# 4_COMMUNICATION.net
KiCad netlist of a schematic drawn in Altium Designer
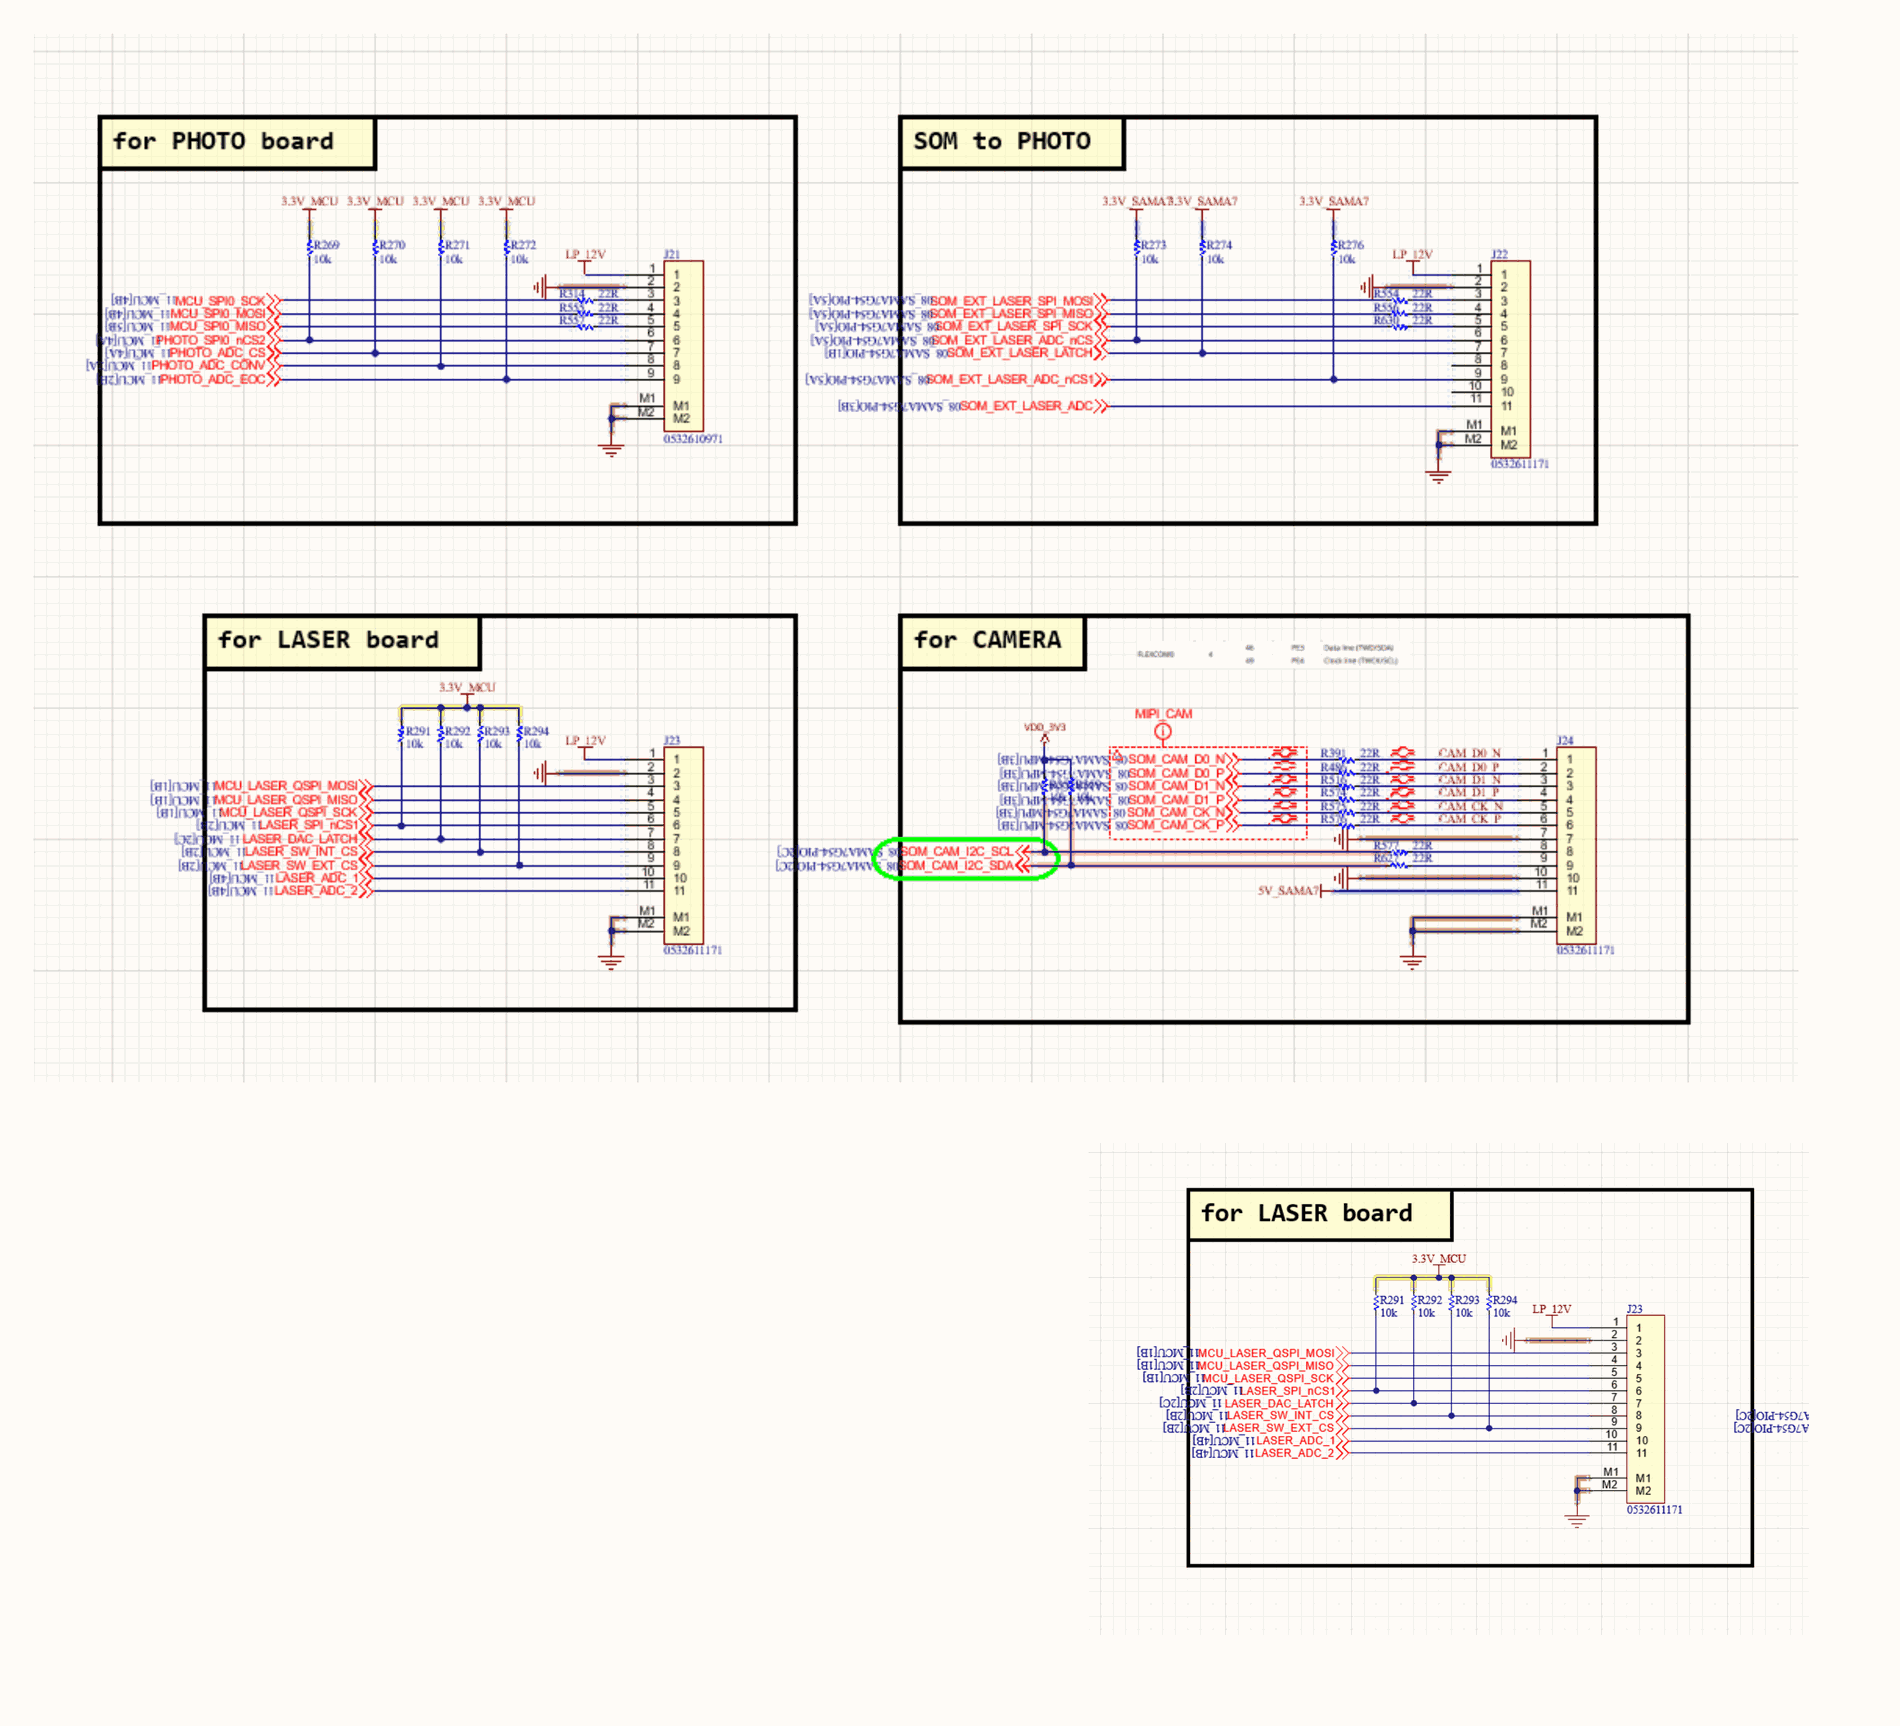
[diagram p0: 4_COMMUNICATION.SchDoc, left]
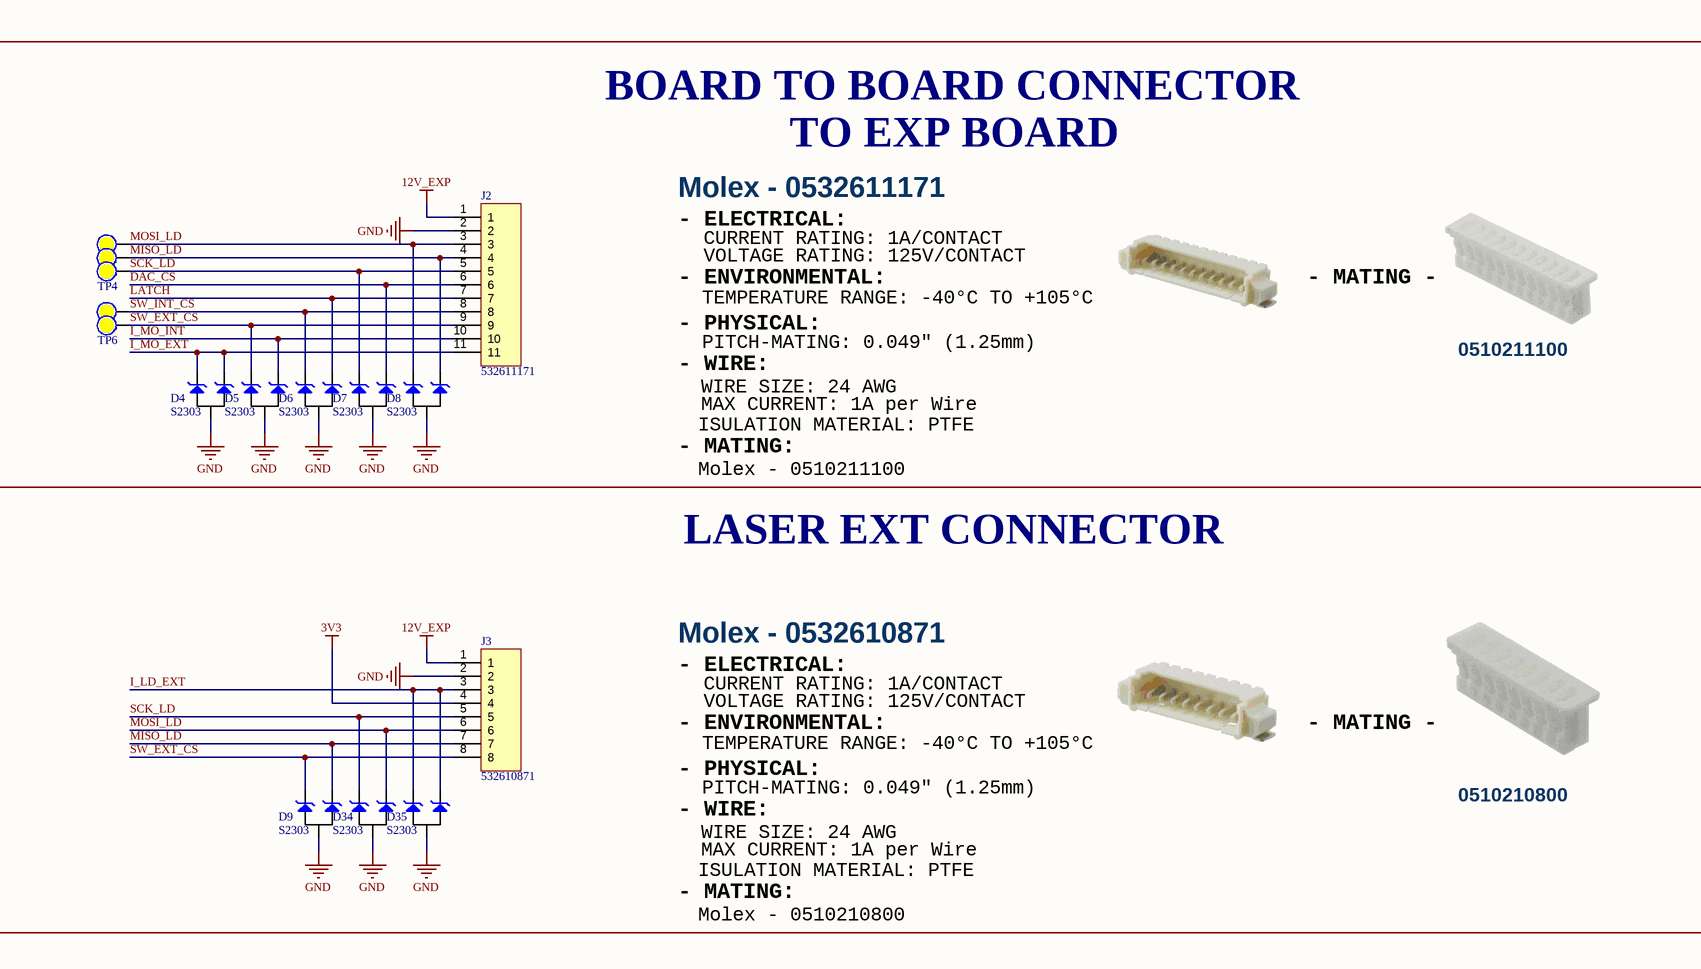
[diagram p1: 4_COMMUNICATION.SchDoc, right]

(export (version "E")
  (design (tool "Eeschema 10.0.6"))
  (components
    (comp (ref "D4")
      (value "S2303")
      (footprint "SOT23-3-132")
      (libsource (lib "LASER_LIB_SCHE") (part "S2303"))
    )
    (comp (ref "D5")
      (value "S2303")
      (footprint "SOT23-3-132")
      (libsource (lib "LASER_LIB_SCHE") (part "S2303"))
    )
    (comp (ref "D6")
      (value "S2303")
      (footprint "SOT23-3-132")
      (libsource (lib "LASER_LIB_SCHE") (part "S2303"))
    )
    (comp (ref "D7")
      (value "S2303")
      (footprint "SOT23-3-132")
      (libsource (lib "LASER_LIB_SCHE") (part "S2303"))
    )
    (comp (ref "D8")
      (value "S2303")
      (footprint "SOT23-3-132")
      (libsource (lib "LASER_LIB_SCHE") (part "S2303"))
    )
    (comp (ref "D9")
      (value "S2303")
      (footprint "SOT23-3-132")
      (libsource (lib "LASER_LIB_SCHE") (part "S2303"))
    )
    (comp (ref "D34")
      (value "S2303")
      (footprint "SOT23-3-132")
      (libsource (lib "LASER_LIB_SCHE") (part "S2303"))
    )
    (comp (ref "D35")
      (value "S2303")
      (footprint "SOT23-3-132")
      (libsource (lib "LASER_LIB_SCHE") (part "S2303"))
    )
    (comp (ref "J2")
      (value "532611171")
      (footprint "MOLEX_0532611171")
      (fields (field (name "COPYRIGHT") "Copyright (C) 2025 Ultra Librarian. All rights reserved."))
      (libsource (lib "LASER_LIB_SCHE") (part "532611171"))
    )
    (comp (ref "J3")
      (value "532610871")
      (footprint "MOLEX_0532610871")
      (fields (field (name "COPYRIGHT") "Copyright (C) 2025 Ultra Librarian. All rights reserved."))
      (libsource (lib "LASER_LIB_SCHE") (part "532610871"))
    )
    (comp (ref "TP2")
      (value "~")
      (footprint "Testpoint_50")
      (description "Test Point")
      (libsource (lib "LASER_LIB_SCHE") (part "Test Point"))
    )
    (comp (ref "TP3")
      (value "~")
      (footprint "Testpoint_50")
      (description "Test Point")
      (libsource (lib "LASER_LIB_SCHE") (part "Test Point"))
    )
    (comp (ref "TP4")
      (value "~")
      (footprint "Testpoint_50")
      (description "Test Point")
      (libsource (lib "LASER_LIB_SCHE") (part "Test Point"))
    )
    (comp (ref "TP5")
      (value "~")
      (footprint "Testpoint_50")
      (description "Test Point")
      (libsource (lib "LASER_LIB_SCHE") (part "Test Point"))
    )
    (comp (ref "TP6")
      (value "~")
      (footprint "Testpoint_50")
      (description "Test Point")
      (libsource (lib "LASER_LIB_SCHE") (part "Test Point"))
    )
  )
  (nets
    (net (code "1") (name "/DAC_CS") (class "Default")
      (node (ref "D7") (pin "1") (pintype "passive"))
      (node (ref "J2") (pin "6") (pinfunction "6_6") (pintype "passive"))
    )
    (net (code "2") (name "/I_LD_EXT") (class "Default")
      (node (ref "D35") (pin "1") (pintype "passive"))
      (node (ref "D35") (pin "2") (pintype "passive"))
      (node (ref "J3") (pin "3") (pinfunction "3_3") (pintype "passive"))
    )
    (net (code "3") (name "/I_MO_EXT") (class "Default")
      (node (ref "D4") (pin "1") (pintype "passive"))
      (node (ref "D4") (pin "2") (pintype "passive"))
      (node (ref "J2") (pin "11") (pinfunction "11_11") (pintype "passive"))
    )
    (net (code "4") (name "/I_MO_INT") (class "Default")
      (node (ref "D5") (pin "1") (pintype "passive"))
      (node (ref "J2") (pin "10") (pinfunction "10_10") (pintype "passive"))
    )
    (net (code "5") (name "/LATCH") (class "Default")
      (node (ref "D6") (pin "1") (pintype "passive"))
      (node (ref "J2") (pin "7") (pinfunction "7_7") (pintype "passive"))
    )
    (net (code "6") (name "/MISO_LD") (class "Default")
      (node (ref "D8") (pin "1") (pintype "passive"))
      (node (ref "D9") (pin "1") (pintype "passive"))
      (node (ref "J2") (pin "4") (pinfunction "4_4") (pintype "passive"))
      (node (ref "J3") (pin "7") (pinfunction "7_7") (pintype "passive"))
      (node (ref "TP3") (pin "1") (pinfunction "1_1") (pintype "passive"))
    )
    (net (code "7") (name "/MOSI_LD") (class "Default")
      (node (ref "D34") (pin "1") (pintype "passive"))
      (node (ref "D8") (pin "2") (pintype "passive"))
      (node (ref "J2") (pin "3") (pinfunction "3_3") (pintype "passive"))
      (node (ref "J3") (pin "6") (pinfunction "6_6") (pintype "passive"))
      (node (ref "TP2") (pin "1") (pinfunction "1_1") (pintype "passive"))
    )
    (net (code "8") (name "/SCK_LD") (class "Default")
      (node (ref "D34") (pin "2") (pintype "passive"))
      (node (ref "D7") (pin "2") (pintype "passive"))
      (node (ref "J2") (pin "5") (pinfunction "5_5") (pintype "passive"))
      (node (ref "J3") (pin "5") (pinfunction "5_5") (pintype "passive"))
      (node (ref "TP4") (pin "1") (pinfunction "1_1") (pintype "passive"))
    )
    (net (code "9") (name "/SW_EXT_CS") (class "Default")
      (node (ref "D5") (pin "2") (pintype "passive"))
      (node (ref "D9") (pin "2") (pintype "passive"))
      (node (ref "J2") (pin "9") (pinfunction "9_9") (pintype "passive"))
      (node (ref "J3") (pin "8") (pinfunction "8_8") (pintype "passive"))
      (node (ref "TP6") (pin "1") (pinfunction "1_1") (pintype "passive"))
    )
    (net (code "10") (name "/SW_INT_CS") (class "Default")
      (node (ref "D6") (pin "2") (pintype "passive"))
      (node (ref "J2") (pin "8") (pinfunction "8_8") (pintype "passive"))
      (node (ref "TP5") (pin "1") (pinfunction "1_1") (pintype "passive"))
    )
    (net (code "11") (name "3V3") (class "Default")
      (node (ref "J3") (pin "4") (pinfunction "4_4") (pintype "passive"))
    )
    (net (code "12") (name "12V_EXP") (class "Default")
      (node (ref "J2") (pin "1") (pinfunction "1_1") (pintype "passive"))
      (node (ref "J3") (pin "1") (pinfunction "1_1") (pintype "passive"))
    )
    (net (code "13") (name "GND") (class "Default")
      (node (ref "D34") (pin "3") (pintype "passive"))
      (node (ref "D35") (pin "3") (pintype "passive"))
      (node (ref "D4") (pin "3") (pintype "passive"))
      (node (ref "D5") (pin "3") (pintype "passive"))
      (node (ref "D6") (pin "3") (pintype "passive"))
      (node (ref "D7") (pin "3") (pintype "passive"))
      (node (ref "D8") (pin "3") (pintype "passive"))
      (node (ref "D9") (pin "3") (pintype "passive"))
      (node (ref "J2") (pin "2") (pinfunction "2_2") (pintype "passive"))
      (node (ref "J3") (pin "2") (pinfunction "2_2") (pintype "passive"))
    )
  )
)
